# USB.net
KiCad netlist of a schematic drawn in Altium Designer
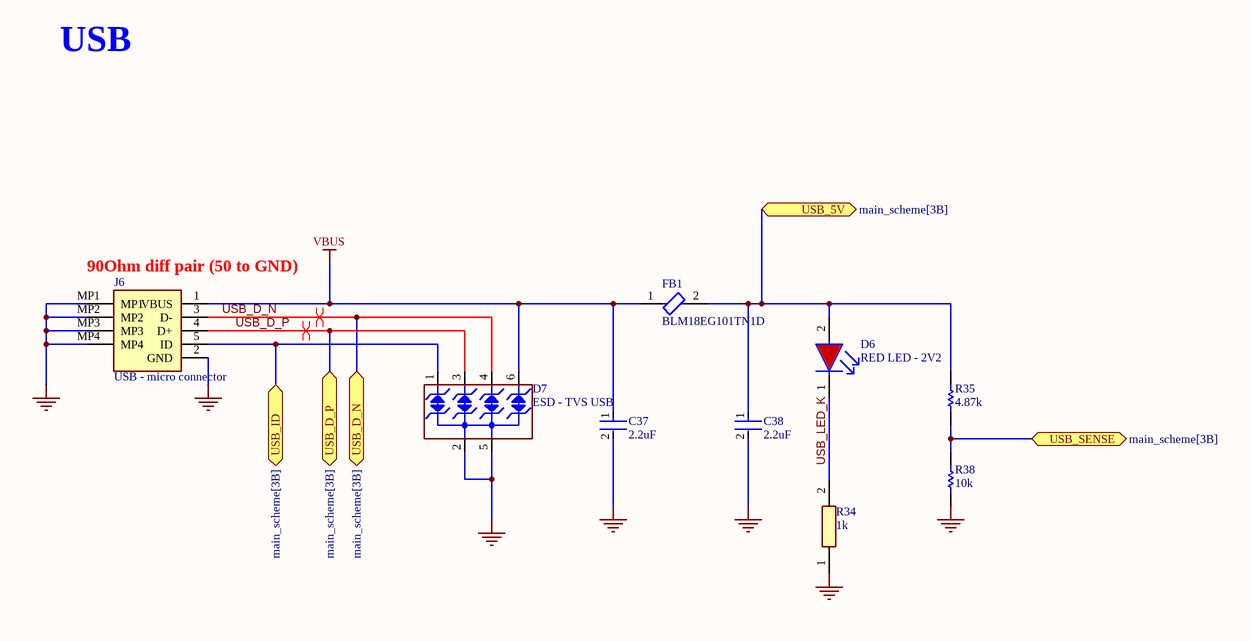
[diagram p0: USB.SchDoc]

(export (version "E")
  (design (tool "Eeschema 10.0.6"))
  (components
    (comp (ref "C37")
      (value "2.2uF")
      (footprint "0603-CAP")
      (description "General Purpose Ceramic Capacitor, 0603,2.2uF,35V,10%")
      (fields (field (name "PARTNUMBER") "C1608JB1V225K080AC"))
      (libsource (lib "Schlib1") (part "CAP-0603-2.2uF"))
    )
    (comp (ref "C38")
      (value "2.2uF")
      (footprint "0603-CAP")
      (description "General Purpose Ceramic Capacitor, 0603,2.2uF,35V,10%")
      (fields (field (name "PARTNUMBER") "C1608JB1V225K080AC"))
      (libsource (lib "Schlib1") (part "CAP-0603-2.2uF"))
    )
    (comp (ref "D6")
      (value "RED LED - 2V2")
      (footprint "0603_RED_LED")
      (description "LED RED DIFFUSED 0603 SMD")
      (fields (field (name "PARTNUMBER") "SML-D12U1WT86"))
      (libsource (lib "Schlib1") (part "LED - 0603 - RED - 2V2"))
    )
    (comp (ref "D7")
      (value "ESD - TVS USB")
      (footprint "SOT23-6L")
      (description "4-line ESD protection")
      (fields (field (name "PARTNUMBER") "ESDA6V1BC6"))
      (libsource (lib "Schlib1") (part "ESD - TVS USB"))
    )
    (comp (ref "FB1")
      (value "BLM18EG101TN1D")
      (footprint "Ferrite_bead")
      (description "Chip Ferrite Bead, 0603, 100Ω @ 100MHz, 25%, 0.045Ω, 2A")
      (libsource (lib "Schlib1") (part "Ferrite_bead - 0603 - 100R"))
    )
    (comp (ref "J6")
      (value "USB - micro connector")
      (footprint "PcbLib1:USB_micro")
      (description "USB Connectors USB jack, 2.0, micro B type, 5 pin, horizontal, gold flash, SMT, TRConnector")
      (fields (field (name "PARTNUMBER") "UJ2-MIBH-G-SMT-TR"))
      (libsource (lib "Schlib1") (part "USB-micro connector"))
    )
    (comp (ref "R34")
      (value "1k")
      (footprint "PcbLib1:0603- SMD resistor")
      (description "Resistor 0603 1KR 100mW 1%")
      (fields (field (name "PARTNUMBER") "RT0603FRE071KL"))
      (libsource (lib "Schlib1") (part "RESISTOR - 0603 - 1k"))
    )
    (comp (ref "R35")
      (value "4.87k")
      (footprint "RESC1005X40X25NL05T05")
      (description "Resistor - 0402 -  4.87k - 1% - 100mW")
      (fields (field (name "PARTNUMBER") "ERJ-2RKF4871X"))
      (libsource (lib "Schlib1") (part "Resistor - 0402 - 4.87k"))
    )
    (comp (ref "R38")
      (value "10k")
      (footprint "RESC1005X40X25NL05T05")
      (description "Resistor - 0402 -  10k - 5% - 125mW")
      (fields (field (name "PARTNUMBER") "RC0402JR-7W10KL"))
      (libsource (lib "Schlib1") (part "Resistor - 0402 -10k"))
    )
  )
  (nets
    (net (code "1") (name "/USB_5V") (class "Default")
      (node (ref "C38") (pin "1") (pinfunction "1_1") (pintype "passive"))
      (node (ref "D6") (pin "2") (pinfunction "A_2") (pintype "passive"))
      (node (ref "FB1") (pin "2") (pinfunction "2_2") (pintype "passive"))
      (node (ref "R35") (pin "1") (pinfunction "1_1") (pintype "passive"))
    )
    (net (code "2") (name "/USB_D_N") (class "Default")
      (node (ref "D7") (pin "4") (pinfunction "IO3_4") (pintype "passive"))
      (node (ref "J6") (pin "3") (pinfunction "D-_3") (pintype "passive"))
    )
    (net (code "3") (name "/USB_D_P") (class "Default")
      (node (ref "D7") (pin "3") (pinfunction "GND_3") (pintype "passive"))
      (node (ref "J6") (pin "4") (pinfunction "D+_4") (pintype "passive"))
    )
    (net (code "4") (name "/USB_ID") (class "Default")
      (node (ref "D7") (pin "1") (pinfunction "IO1_1") (pintype "passive"))
      (node (ref "J6") (pin "5") (pinfunction "ID_5") (pintype "passive"))
    )
    (net (code "5") (name "/USB_LED_K") (class "Default")
      (node (ref "D6") (pin "1") (pinfunction "C_1") (pintype "passive"))
      (node (ref "R34") (pin "2") (pinfunction "2_2") (pintype "passive"))
    )
    (net (code "6") (name "/USB_SENSE") (class "Default")
      (node (ref "R35") (pin "2") (pinfunction "2_2") (pintype "passive"))
      (node (ref "R38") (pin "1") (pinfunction "1_1") (pintype "passive"))
    )
    (net (code "7") (name "GND") (class "Default")
      (node (ref "C37") (pin "2") (pinfunction "2_2") (pintype "passive"))
      (node (ref "C38") (pin "2") (pinfunction "2_2") (pintype "passive"))
      (node (ref "D7") (pin "2") (pinfunction "IO2_2") (pintype "passive"))
      (node (ref "D7") (pin "5") (pinfunction "IO4_5") (pintype "passive"))
      (node (ref "J6") (pin "2") (pinfunction "GND_2") (pintype "passive"))
      (node (ref "J6") (pin "MP1") (pinfunction "MP1_MP1") (pintype "passive"))
      (node (ref "J6") (pin "MP2") (pinfunction "MP2_MP2") (pintype "passive"))
      (node (ref "J6") (pin "MP3") (pinfunction "MP3_MP3") (pintype "passive"))
      (node (ref "J6") (pin "MP4") (pinfunction "MP4_MP4") (pintype "passive"))
      (node (ref "R34") (pin "1") (pinfunction "1_1") (pintype "passive"))
      (node (ref "R38") (pin "2") (pinfunction "2_2") (pintype "passive"))
    )
    (net (code "8") (name "VBUS") (class "Default")
      (node (ref "C37") (pin "1") (pinfunction "1_1") (pintype "passive"))
      (node (ref "D7") (pin "6") (pinfunction "NC_6") (pintype "passive"))
      (node (ref "FB1") (pin "1") (pinfunction "1_1") (pintype "passive"))
      (node (ref "J6") (pin "1") (pinfunction "VBUS_1") (pintype "passive"))
    )
  )
)
